# 08_-_COMMUNICATION.net
KiCad netlist of a schematic drawn in Altium Designer
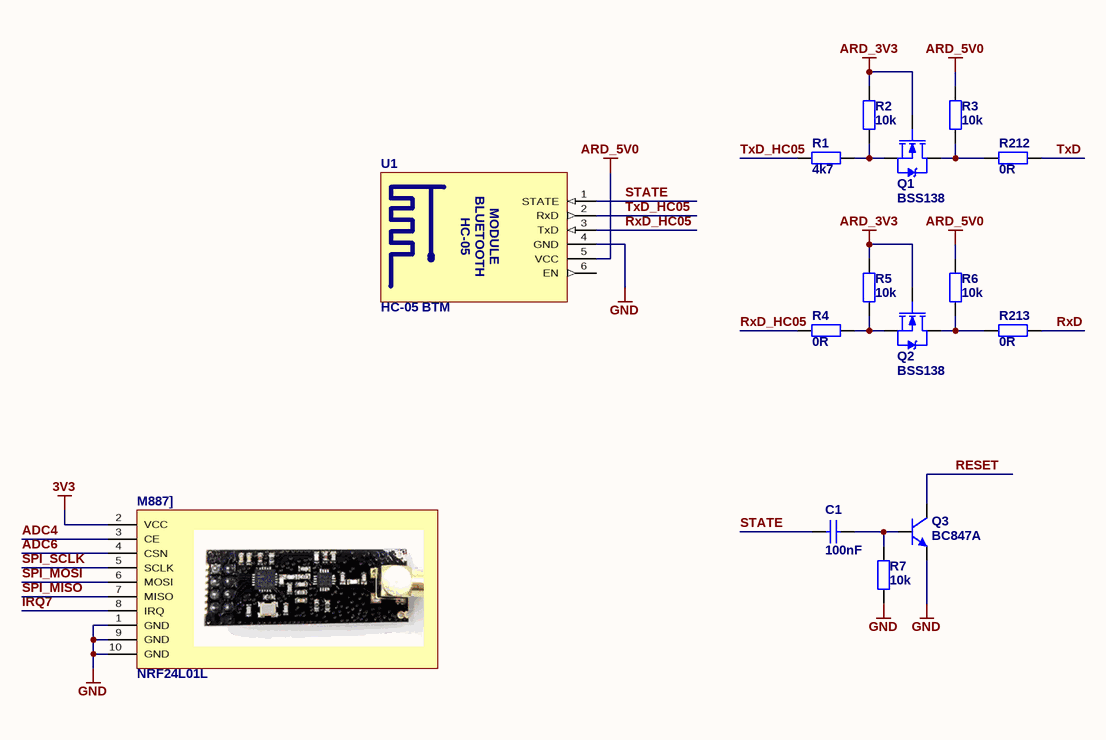
[diagram p0: [08] - COMMUNICATION.SchDoc]

(export (version "E")
  (design (tool "Eeschema 10.0.6"))
  (components
    (comp (ref "C1")
      (value "100nF")
      (footprint "C0805")
      (description "Capacitor")
      (libsource (lib "capacitors") (part "Cap"))
    )
    (comp (ref "M887]")
      (value "NRF24L01L")
      (footprint "NRF24L01L")
      (description "Long Range Wireless Module R2 (1.1KM, PA+SMA)")
      (libsource (lib "wireless_modules") (part "NRF24L01L"))
    )
    (comp (ref "Q1")
      (value "BSS138")
      (footprint "SOT-23")
      (description "N-Channel Enhancement Mode Vertical DMOS FET")
      (fields (field (name "PUBLISHER") "Altium Limited"))
      (libsource (lib "transistors_mos") (part "BSS138"))
    )
    (comp (ref "Q2")
      (value "BSS138")
      (footprint "SOT-23")
      (description "N-Channel Enhancement Mode Vertical DMOS FET")
      (fields (field (name "PUBLISHER") "Altium Limited"))
      (libsource (lib "transistors_mos") (part "BSS138"))
    )
    (comp (ref "Q3")
      (value "BC847A")
      (footprint "SOT-23")
      (description "NPN General Purpose Transistor (VCE=45V, IC=100mA, HFE=110-220)")
      (libsource (lib "transistors_bjt") (part "BC847A"))
    )
    (comp (ref "R1")
      (value "4k7")
      (footprint "R0805")
      (description "Resistor")
      (libsource (lib "resistors") (part "Res"))
    )
    (comp (ref "R2")
      (value "10k")
      (footprint "R0805")
      (description "Resistor")
      (libsource (lib "") (part "Res_1"))
    )
    (comp (ref "R3")
      (value "10k")
      (footprint "R0805")
      (description "Resistor")
      (libsource (lib "") (part "Res_1"))
    )
    (comp (ref "R4")
      (value "0R")
      (footprint "R0805")
      (description "Resistor")
      (libsource (lib "resistors") (part "Res"))
    )
    (comp (ref "R5")
      (value "10k")
      (footprint "R0805")
      (description "Resistor")
      (libsource (lib "") (part "Res_1"))
    )
    (comp (ref "R6")
      (value "10k")
      (footprint "R0805")
      (description "Resistor")
      (libsource (lib "") (part "Res_1"))
    )
    (comp (ref "R7")
      (value "10k")
      (footprint "R0805")
      (description "Resistor")
      (libsource (lib "") (part "Res_1"))
    )
    (comp (ref "R212")
      (value "0R")
      (footprint "R0805")
      (description "Resistor")
      (libsource (lib "resistors") (part "Res"))
    )
    (comp (ref "R213")
      (value "0R")
      (footprint "R0805")
      (description "Resistor")
      (libsource (lib "resistors") (part "Res"))
    )
    (comp (ref "U1")
      (value "HC-05 BTM")
      (footprint "HC-05_H")
      (description "HC-05 Bluetooth Module")
      (libsource (lib "wireless_modules") (part "HC-05_BTM"))
    )
  )
  (nets
    (net (code "1") (name "/ADC4") (class "Default")
      (node (ref "M887]") (pin "3") (pinfunction "CE_3") (pintype "passive"))
    )
    (net (code "2") (name "/ADC6") (class "Default")
      (node (ref "M887]") (pin "4") (pinfunction "CSN_4") (pintype "passive"))
    )
    (net (code "3") (name "/IRQ7") (class "Default")
      (node (ref "M887]") (pin "8") (pinfunction "IRQ_8") (pintype "passive"))
    )
    (net (code "4") (name "/RESET") (class "Default")
      (node (ref "Q3") (pin "3") (pinfunction "C_3") (pintype "passive"))
    )
    (net (code "5") (name "/RxD") (class "Default")
      (node (ref "R213") (pin "2") (pinfunction "2_2") (pintype "passive"))
    )
    (net (code "6") (name "/RxD_HC05") (class "Default")
      (node (ref "R4") (pin "1") (pinfunction "1_1") (pintype "passive"))
      (node (ref "U1") (pin "3") (pinfunction "TxD_3") (pintype "input"))
    )
    (net (code "7") (name "/SPI_MISO") (class "Default")
      (node (ref "M887]") (pin "7") (pinfunction "MISO_7") (pintype "passive"))
    )
    (net (code "8") (name "/SPI_MOSI") (class "Default")
      (node (ref "M887]") (pin "6") (pinfunction "MOSI_6") (pintype "passive"))
    )
    (net (code "9") (name "/SPI_SCLK") (class "Default")
      (node (ref "M887]") (pin "5") (pinfunction "SCLK_5") (pintype "passive"))
    )
    (net (code "10") (name "/STATE") (class "Default")
      (node (ref "C1") (pin "1") (pinfunction "1_1") (pintype "passive"))
      (node (ref "U1") (pin "1") (pinfunction "STATE_1") (pintype "input"))
    )
    (net (code "11") (name "/TxD") (class "Default")
      (node (ref "R212") (pin "2") (pinfunction "2_2") (pintype "passive"))
    )
    (net (code "12") (name "/TxD_HC05") (class "Default")
      (node (ref "R1") (pin "1") (pinfunction "1_1") (pintype "passive"))
      (node (ref "U1") (pin "2") (pinfunction "RxD_2") (pintype "output"))
    )
    (net (code "13") (name "3V3") (class "Default")
      (node (ref "M887]") (pin "2") (pinfunction "VCC_2") (pintype "passive"))
    )
    (net (code "14") (name "ARD_3V3") (class "Default")
      (node (ref "Q1") (pin "1") (pinfunction "G_1") (pintype "passive"))
      (node (ref "Q2") (pin "1") (pinfunction "G_1") (pintype "passive"))
      (node (ref "R2") (pin "1") (pinfunction "1_1") (pintype "passive"))
      (node (ref "R5") (pin "1") (pinfunction "1_1") (pintype "passive"))
    )
    (net (code "15") (name "ARD_5V0") (class "Default")
      (node (ref "R3") (pin "1") (pinfunction "1_1") (pintype "passive"))
      (node (ref "R6") (pin "1") (pinfunction "1_1") (pintype "passive"))
      (node (ref "U1") (pin "5") (pinfunction "VCC_5") (pintype "power_in"))
    )
    (net (code "16") (name "GND") (class "Default")
      (node (ref "M887]") (pin "1") (pinfunction "GND_1") (pintype "passive"))
      (node (ref "M887]") (pin "10") (pinfunction "GND_10") (pintype "passive"))
      (node (ref "M887]") (pin "9") (pinfunction "GND_9") (pintype "passive"))
      (node (ref "Q3") (pin "2") (pinfunction "E_2") (pintype "passive"))
      (node (ref "R7") (pin "2") (pinfunction "2_2") (pintype "passive"))
      (node (ref "U1") (pin "4") (pinfunction "GND_4") (pintype "power_in"))
    )
    (net (code "17") (name "Net-(Q1-D)") (class "Default")
      (node (ref "Q1") (pin "3") (pinfunction "D_3") (pintype "passive"))
      (node (ref "R212") (pin "1") (pinfunction "1_1") (pintype "passive"))
      (node (ref "R3") (pin "2") (pinfunction "2_2") (pintype "passive"))
    )
    (net (code "18") (name "Net-(Q1-S)") (class "Default")
      (node (ref "Q1") (pin "2") (pinfunction "S_2") (pintype "passive"))
      (node (ref "R1") (pin "2") (pinfunction "2_2") (pintype "passive"))
      (node (ref "R2") (pin "2") (pinfunction "2_2") (pintype "passive"))
    )
    (net (code "19") (name "Net-(Q2-D)") (class "Default")
      (node (ref "Q2") (pin "3") (pinfunction "D_3") (pintype "passive"))
      (node (ref "R213") (pin "1") (pinfunction "1_1") (pintype "passive"))
      (node (ref "R6") (pin "2") (pinfunction "2_2") (pintype "passive"))
    )
    (net (code "20") (name "Net-(Q2-S)") (class "Default")
      (node (ref "Q2") (pin "2") (pinfunction "S_2") (pintype "passive"))
      (node (ref "R4") (pin "2") (pinfunction "2_2") (pintype "passive"))
      (node (ref "R5") (pin "2") (pinfunction "2_2") (pintype "passive"))
    )
    (net (code "21") (name "Net-(Q3-B)") (class "Default")
      (node (ref "C1") (pin "2") (pinfunction "2_2") (pintype "passive"))
      (node (ref "Q3") (pin "1") (pinfunction "B_1") (pintype "passive"))
      (node (ref "R7") (pin "1") (pinfunction "1_1") (pintype "passive"))
    )
    (net (code "22") (name "unconnected-(U1-EN-Pad6)") (class "Default")
      (node (ref "U1") (pin "6") (pinfunction "EN_6") (pintype "output"))
    )
  )
)
